# v1_0.net
KiCad netlist of a schematic drawn in Altium Designer
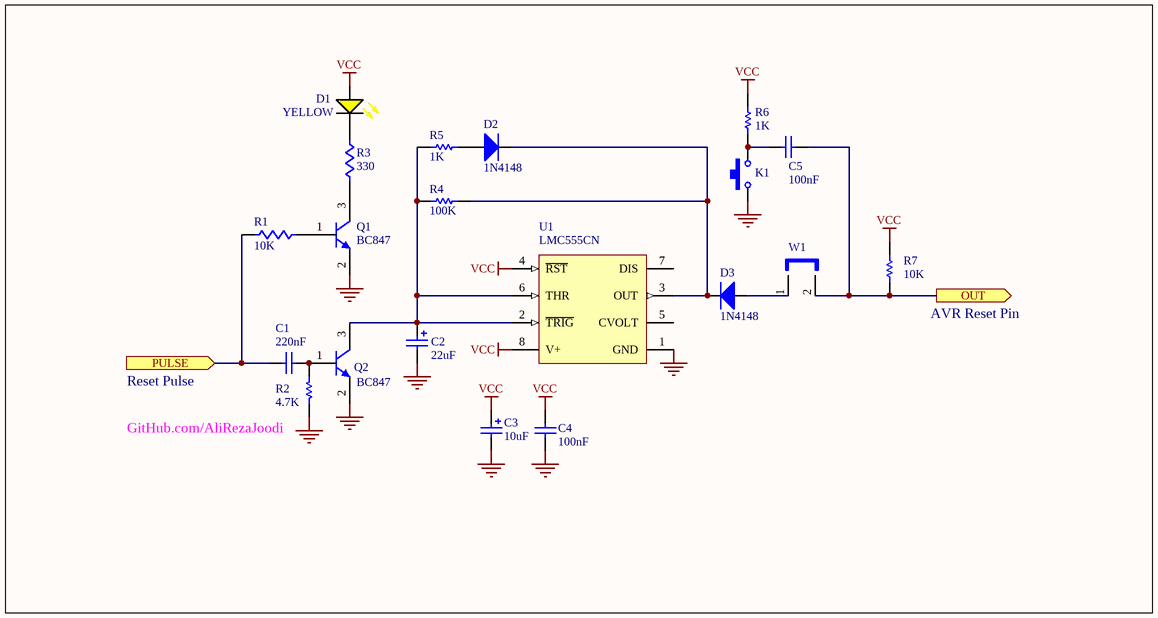
[diagram p0: v1.0.SchDoc]

(export (version "E")
  (design (tool "Eeschema 10.0.6"))
  (components
    (comp (ref "C1")
      (value "220nF")
      (footprint "RESC3216N")
      (description "Capacitor")
      (fields (field (name "Comment") "Cap") (field (name "PUBLISHER") "Altium Limited"))
      (libsource (lib "Miscellaneous Devices") (part "Cap"))
    )
    (comp (ref "C2")
      (value "22uF")
      (footprint "Cap_B")
      (description "Polarized Capacitor (Radial)")
      (fields
        (field (name "MANUFACTURER") "Generic Components")
        (field (name "Comment") "Capacitor")
        (field (name "PUBLISHER") "Altium Limited")
      )
      (libsource (lib "Miscellaneous Devices") (part "Cap Pol1"))
    )
    (comp (ref "C3")
      (value "10uF")
      (footprint "Cap_B")
      (description "Polarized Capacitor (Radial)")
      (fields
        (field (name "MANUFACTURER") "Generic Components")
        (field (name "Comment") "Capacitor")
        (field (name "PUBLISHER") "Altium Limited")
      )
      (libsource (lib "Miscellaneous Devices") (part "Cap Pol1"))
    )
    (comp (ref "C4")
      (value "100nF")
      (footprint "0805")
      (description "Capacitor")
      (fields
        (field (name "MANUFACTURER") "Generic Components")
        (field (name "Comment") "Cap")
        (field (name "PUBLISHER") "Altium Limited")
      )
      (libsource (lib "Miscellaneous Devices") (part "Cap"))
    )
    (comp (ref "C5")
      (value "100nF")
      (footprint "0805")
      (description "Capacitor")
      (fields
        (field (name "MANUFACTURER") "Generic Components")
        (field (name "Comment") "Cap")
        (field (name "PUBLISHER") "Altium Limited")
      )
      (libsource (lib "Miscellaneous Devices") (part "Cap"))
    )
    (comp (ref "D1")
      (value "YELLOW")
      (footprint "LED_THD_3MM_YELLOW_R")
      (description "LED, Yellow")
      (fields (field (name "MANUFACTURER") "Generic Components") (field (name "PUBLISHER") "Altium Limited"))
      (libsource (lib "Display") (part "LED_YELLOW"))
    )
    (comp (ref "D2")
      (value "1N4148")
      (footprint "0805_Diode")
      (description "Default Diode")
      (fields
        (field (name "MANUFACTURER") "Generic Components")
        (field (name "Comment") "Diode")
        (field (name "PUBLISHER") "Altium Limited")
      )
      (libsource (lib "Miscellaneous Devices") (part "Diode"))
    )
    (comp (ref "D3")
      (value "1N4148")
      (footprint "0805_Diode")
      (description "Default Diode")
      (fields
        (field (name "MANUFACTURER") "Generic Components")
        (field (name "Comment") "Diode")
        (field (name "PUBLISHER") "Altium Limited")
      )
      (libsource (lib "Miscellaneous Devices") (part "Diode"))
    )
    (comp (ref "K1")
      (value "Switch_SW-PB")
      (footprint "SWPBT_SPST_6X6X4")
      (description "Switch, SW-PB")
      (fields (field (name "MANUFACTURER") "Generic Components") (field (name "PUBLISHER") "Altium Limited"))
      (libsource (lib "Passive") (part "Switch_SW-PB_2Form"))
    )
    (comp (ref "Q1")
      (value "BC847")
      (footprint "SOT23-3N")
      (description "Silicon Bipolar Transistor")
      (fields (field (name "Comment") "NPN"))
      (libsource (lib "my Libraries") (part "BC847"))
    )
    (comp (ref "Q2")
      (value "BC847")
      (footprint "SOT23-3N")
      (description "Silicon Bipolar Transistor")
      (fields (field (name "Comment") "NPN"))
      (libsource (lib "my Libraries") (part "BC847"))
    )
    (comp (ref "R1")
      (value "10K")
      (footprint "0805")
      (description "Resistor")
      (fields
        (field (name "MANUFACTURER") "Generic Components")
        (field (name "Comment") "RES")
        (field (name "PUBLISHER") "Altium Limited")
      )
      (libsource (lib "") (part "Res1_1"))
    )
    (comp (ref "R2")
      (value "4.7K")
      (footprint "0805")
      (description "Resistor")
      (fields (field (name "Comment") "Res1") (field (name "PUBLISHER") "Altium Limited"))
      (libsource (lib "Miscellaneous Devices") (part "Res1"))
    )
    (comp (ref "R3")
      (value "330")
      (footprint "0805")
      (description "Resistor")
      (fields
        (field (name "MANUFACTURER") "Generic Components")
        (field (name "Comment") "RES")
        (field (name "PUBLISHER") "Altium Limited")
      )
      (libsource (lib "") (part "Res1_1"))
    )
    (comp (ref "R4")
      (value "100K")
      (footprint "0805")
      (description "Resistor")
      (fields (field (name "Comment") "Res1") (field (name "PUBLISHER") "Altium Limited"))
      (libsource (lib "Miscellaneous Devices") (part "Res1"))
    )
    (comp (ref "R5")
      (value "1K")
      (footprint "0805")
      (description "Resistor")
      (fields (field (name "Comment") "Res1") (field (name "PUBLISHER") "Altium Limited"))
      (libsource (lib "Miscellaneous Devices") (part "Res1"))
    )
    (comp (ref "R6")
      (value "1K")
      (footprint "0805")
      (description "Resistor")
      (fields (field (name "MANUFACTURER") "Generic Components") (field (name "PUBLISHER") "Altium Limited"))
      (libsource (lib "Miscellaneous Devices") (part "Res1"))
    )
    (comp (ref "R7")
      (value "10K")
      (footprint "0805")
      (description "Resistor")
      (fields
        (field (name "MANUFACTURER") "Generic Components")
        (field (name "Comment") "Res1")
        (field (name "PUBLISHER") "Altium Limited")
      )
      (libsource (lib "Miscellaneous Devices") (part "Res1"))
    )
    (comp (ref "U1")
      (value "LMC555CN")
      (footprint "SOP127P636-8N")
      (description "CMOS Timer, 8-pin MDIP")
      (fields
        (field (name "MANUFACTURER") "National Semiconductor")
        (field (name "PUBLISHER") "Altium Limited")
      )
      (libsource (lib "NSC Analog") (part "LMC555CN"))
    )
    (comp (ref "W1")
      (value "Jumper 2pin")
      (footprint "HDR1X2")
      (description "Jumper Wire")
      (fields (field (name "MANUFACTURER") "Generic Components") (field (name "PUBLISHER") "Altium Limited"))
      (libsource (lib "my Libraries") (part "Jumper 2pin"))
    )
  )
  (nets
    (net (code "1") (name "/OUT") (class "Default")
      (node (ref "C5") (pin "1") (pinfunction "1_1") (pintype "passive"))
      (node (ref "R7") (pin "2") (pinfunction "2_2") (pintype "passive"))
      (node (ref "W1") (pin "2") (pinfunction "2_2") (pintype "passive"))
    )
    (net (code "2") (name "/PULSE") (class "Default")
      (node (ref "C1") (pin "1") (pinfunction "1_1") (pintype "passive"))
      (node (ref "R1") (pin "1") (pinfunction "1_1") (pintype "passive"))
    )
    (net (code "3") (name "GND") (class "Default")
      (node (ref "C2") (pin "2") (pinfunction "2_2") (pintype "passive"))
      (node (ref "C3") (pin "2") (pinfunction "2_2") (pintype "passive"))
      (node (ref "C4") (pin "1") (pinfunction "1_1") (pintype "passive"))
      (node (ref "K1") (pin "1") (pinfunction "1_1") (pintype "passive"))
      (node (ref "Q1") (pin "2") (pinfunction "E_2") (pintype "passive"))
      (node (ref "Q2") (pin "2") (pinfunction "E_2") (pintype "passive"))
      (node (ref "R2") (pin "2") (pinfunction "2_2") (pintype "passive"))
      (node (ref "U1") (pin "1") (pinfunction "GND_1") (pintype "power_in"))
    )
    (net (code "4") (name "Net-(C5-Pad2)") (class "Default")
      (node (ref "C5") (pin "2") (pinfunction "2_2") (pintype "passive"))
      (node (ref "K1") (pin "2") (pinfunction "2_2") (pintype "passive"))
      (node (ref "R6") (pin "2") (pinfunction "2_2") (pintype "passive"))
    )
    (net (code "5") (name "Net-(D1-K)") (class "Default")
      (node (ref "D1") (pin "2") (pinfunction "K_2") (pintype "passive"))
      (node (ref "R3") (pin "1") (pinfunction "1_1") (pintype "passive"))
    )
    (net (code "6") (name "Net-(D2-A)") (class "Default")
      (node (ref "D2") (pin "1") (pinfunction "A_1") (pintype "passive"))
      (node (ref "R5") (pin "2") (pinfunction "2_2") (pintype "passive"))
    )
    (net (code "7") (name "Net-(D2-K)") (class "Default")
      (node (ref "D2") (pin "2") (pinfunction "K_2") (pintype "passive"))
      (node (ref "D3") (pin "2") (pinfunction "K_2") (pintype "passive"))
      (node (ref "R4") (pin "2") (pinfunction "2_2") (pintype "passive"))
      (node (ref "U1") (pin "3") (pinfunction "OUT_3") (pintype "output"))
    )
    (net (code "8") (name "Net-(D3-A)") (class "Default")
      (node (ref "D3") (pin "1") (pinfunction "A_1") (pintype "passive"))
      (node (ref "W1") (pin "1") (pinfunction "1_1") (pintype "passive"))
    )
    (net (code "9") (name "Net-(Q1-B)") (class "Default")
      (node (ref "Q1") (pin "1") (pinfunction "B_1") (pintype "passive"))
      (node (ref "R1") (pin "2") (pinfunction "2_2") (pintype "passive"))
    )
    (net (code "10") (name "Net-(Q1-C)") (class "Default")
      (node (ref "Q1") (pin "3") (pinfunction "C_3") (pintype "passive"))
      (node (ref "R3") (pin "2") (pinfunction "2_2") (pintype "passive"))
    )
    (net (code "11") (name "Net-(Q2-B)") (class "Default")
      (node (ref "C1") (pin "2") (pinfunction "2_2") (pintype "passive"))
      (node (ref "Q2") (pin "1") (pinfunction "B_1") (pintype "passive"))
      (node (ref "R2") (pin "1") (pinfunction "1_1") (pintype "passive"))
    )
    (net (code "12") (name "Net-(Q2-C)") (class "Default")
      (node (ref "C2") (pin "1") (pinfunction "1_1") (pintype "passive"))
      (node (ref "Q2") (pin "3") (pinfunction "C_3") (pintype "passive"))
      (node (ref "R4") (pin "1") (pinfunction "1_1") (pintype "passive"))
      (node (ref "R5") (pin "1") (pinfunction "1_1") (pintype "passive"))
      (node (ref "U1") (pin "2") (pinfunction "~{TRIG}_2") (pintype "input"))
      (node (ref "U1") (pin "6") (pinfunction "THR_6") (pintype "input"))
    )
    (net (code "13") (name "VCC") (class "Default")
      (node (ref "C3") (pin "1") (pinfunction "1_1") (pintype "passive"))
      (node (ref "C4") (pin "2") (pinfunction "2_2") (pintype "passive"))
      (node (ref "D1") (pin "1") (pinfunction "A_1") (pintype "passive"))
      (node (ref "R6") (pin "1") (pinfunction "1_1") (pintype "passive"))
      (node (ref "R7") (pin "1") (pinfunction "1_1") (pintype "passive"))
      (node (ref "U1") (pin "4") (pinfunction "~{RST}_4") (pintype "input"))
      (node (ref "U1") (pin "8") (pinfunction "V+_8") (pintype "power_in"))
    )
    (net (code "14") (name "unconnected-(U1-CVOLT-Pad5)") (class "Default")
      (node (ref "U1") (pin "5") (pinfunction "CVOLT_5") (pintype "passive"))
    )
    (net (code "15") (name "unconnected-(U1-DIS-Pad7)") (class "Default")
      (node (ref "U1") (pin "7") (pinfunction "DIS_7") (pintype "open_collector"))
    )
  )
)
